# cardV3.net
KiCad netlist of a schematic drawn in EAGLE
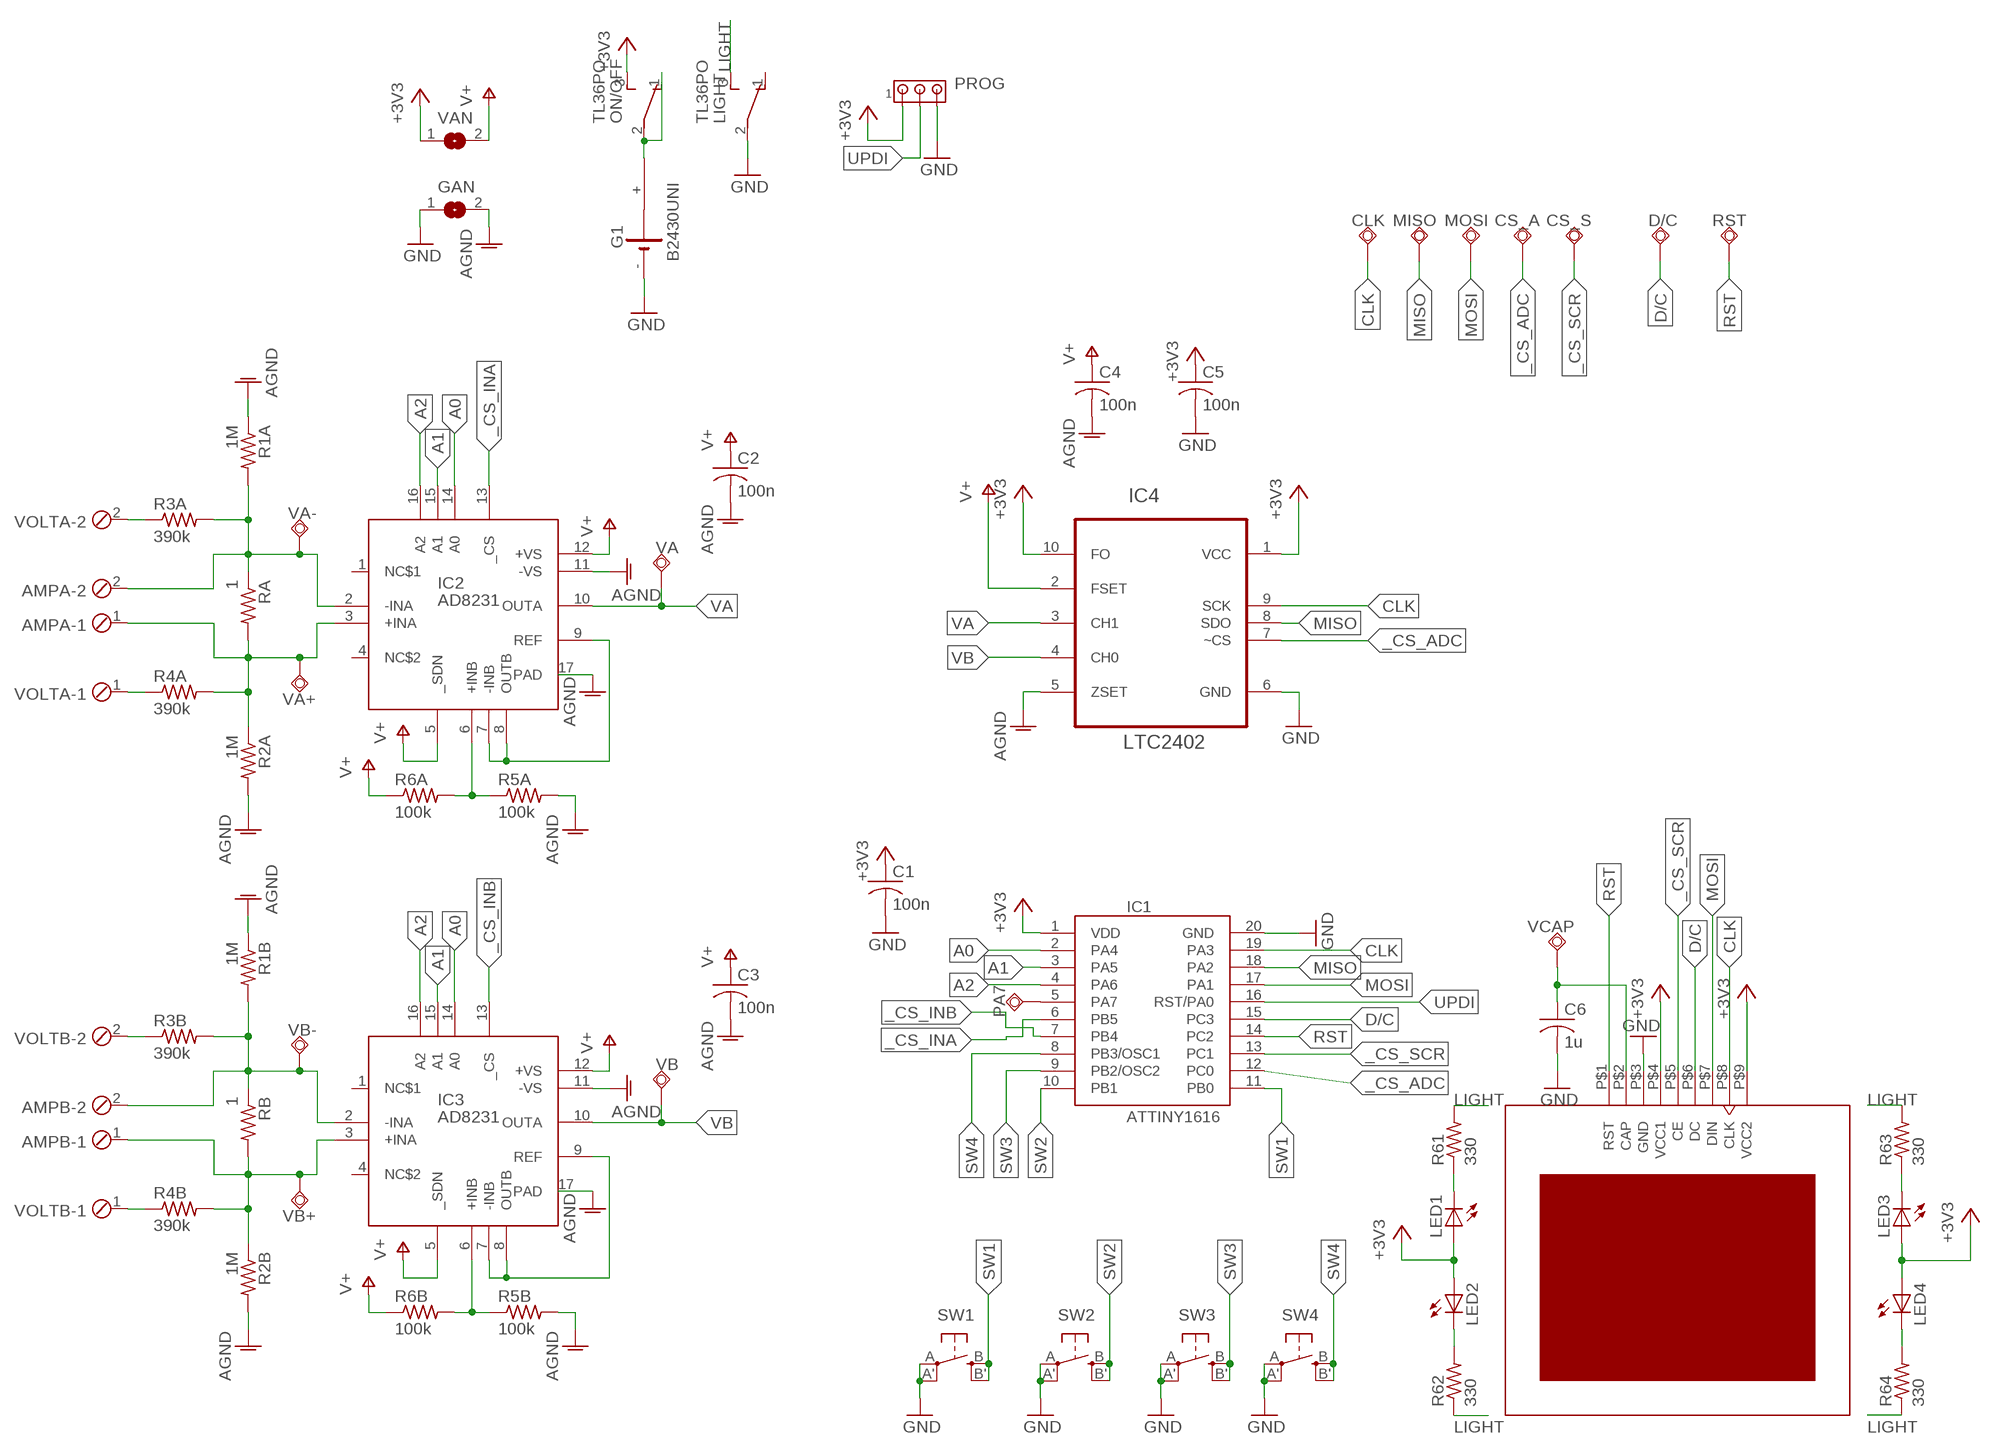
[diagram p0: schematic, sheet 1]

(export (version "E")
  (design (tool "Eeschema 10.0.6"))
  (components
    (comp (ref "AMPA")
      (value "MPT2")
      (footprint "eagle-import:2POL254")
      (libsource (lib "eagle-import") (part "MPT2"))
    )
    (comp (ref "AMPB")
      (value "MPT2")
      (footprint "eagle-import:2POL254")
      (libsource (lib "eagle-import") (part "MPT2"))
    )
    (comp (ref "C1")
      (value "100n")
      (footprint "eagle-import:C0805K")
      (libsource (lib "eagle-import") (part "C-USC0805K"))
    )
    (comp (ref "C2")
      (value "100n")
      (footprint "eagle-import:C0805K")
      (libsource (lib "eagle-import") (part "C-USC0805K"))
    )
    (comp (ref "C3")
      (value "100n")
      (footprint "eagle-import:C0805K")
      (libsource (lib "eagle-import") (part "C-USC0805K"))
    )
    (comp (ref "C4")
      (value "100n")
      (footprint "eagle-import:C0805K")
      (libsource (lib "eagle-import") (part "C-USC0805K"))
    )
    (comp (ref "C5")
      (value "100n")
      (footprint "eagle-import:C0805K")
      (libsource (lib "eagle-import") (part "C-USC0805K"))
    )
    (comp (ref "C6")
      (value "1u")
      (footprint "eagle-import:C0805")
      (libsource (lib "eagle-import") (part "resistor_C-USC0805"))
    )
    (comp (ref "CLK")
      (value "TPSQB1,27")
      (footprint "eagle-import:B1,27")
      (libsource (lib "eagle-import") (part "TPSQB1,27"))
    )
    (comp (ref "CS_A")
      (value "TPSQB1,27")
      (footprint "eagle-import:B1,27")
      (libsource (lib "eagle-import") (part "TPSQB1,27"))
    )
    (comp (ref "CS_S")
      (value "TPSQB1,27")
      (footprint "eagle-import:B1,27")
      (libsource (lib "eagle-import") (part "TPSQB1,27"))
    )
    (comp (ref "D/C")
      (value "TPSQB1,27")
      (footprint "eagle-import:B1,27")
      (libsource (lib "eagle-import") (part "TPSQB1,27"))
    )
    (comp (ref "G1")
      (value "B2430UNI")
      (footprint "eagle-import:B2430UNI")
      (libsource (lib "eagle-import") (part "B2430UNI"))
    )
    (comp (ref "GAN") (value "SJ") (footprint "eagle-import:SJ") (libsource (lib "eagle-import") (part "SJ")))
    (comp (ref "IC1")
      (value "ATTINY1616")
      (footprint "eagle-import:SO20W")
      (libsource (lib "eagle-import") (part "ATTINY1616"))
    )
    (comp (ref "IC2")
      (value "AD8231")
      (footprint "eagle-import:LFCSP16")
      (libsource (lib "eagle-import") (part "AD8231"))
    )
    (comp (ref "IC3")
      (value "AD8231")
      (footprint "eagle-import:LFCSP16")
      (libsource (lib "eagle-import") (part "AD8231"))
    )
    (comp (ref "IC4")
      (value "LTC2402")
      (footprint "eagle-import:MSOP10")
      (libsource (lib "eagle-import") (part "LTC2402CMS"))
    )
    (comp (ref "LED1")
      (value "LEDCHIP-LED0805")
      (footprint "eagle-import:CHIP-LED0805")
      (libsource (lib "eagle-import") (part "LEDCHIP-LED0805"))
    )
    (comp (ref "LED2")
      (value "LEDCHIP-LED0805")
      (footprint "eagle-import:CHIP-LED0805")
      (libsource (lib "eagle-import") (part "LEDCHIP-LED0805"))
    )
    (comp (ref "LED3")
      (value "LEDCHIP-LED0805")
      (footprint "eagle-import:CHIP-LED0805")
      (libsource (lib "eagle-import") (part "LEDCHIP-LED0805"))
    )
    (comp (ref "LED4")
      (value "LEDCHIP-LED0805")
      (footprint "eagle-import:CHIP-LED0805")
      (libsource (lib "eagle-import") (part "LEDCHIP-LED0805"))
    )
    (comp (ref "LIGHT")
      (value "TL36PO")
      (footprint "eagle-import:TL3XPO")
      (libsource (lib "eagle-import") (part "TL36PO"))
    )
    (comp (ref "MISO")
      (value "TPSQB1,27")
      (footprint "eagle-import:B1,27")
      (libsource (lib "eagle-import") (part "TPSQB1,27"))
    )
    (comp (ref "MOSI")
      (value "TPSQB1,27")
      (footprint "eagle-import:B1,27")
      (libsource (lib "eagle-import") (part "TPSQB1,27"))
    )
    (comp (ref "ON/OFF")
      (value "TL36PO")
      (footprint "eagle-import:TL3XPO")
      (libsource (lib "eagle-import") (part "TL36PO"))
    )
    (comp (ref "PA7")
      (value "TPSQB1,27")
      (footprint "eagle-import:B1,27")
      (libsource (lib "eagle-import") (part "TPSQB1,27"))
    )
    (comp (ref "PROG")
      (value "MTA03-100")
      (footprint "eagle-import:10X03MTA")
      (libsource (lib "eagle-import") (part "MTA03-100"))
    )
    (comp (ref "R1A")
      (value "1M")
      (footprint "eagle-import:M0805")
      (libsource (lib "eagle-import") (part "R-US_M0805"))
    )
    (comp (ref "R1B")
      (value "1M")
      (footprint "eagle-import:M0805")
      (libsource (lib "eagle-import") (part "R-US_M0805"))
    )
    (comp (ref "R2A")
      (value "1M")
      (footprint "eagle-import:M0805")
      (libsource (lib "eagle-import") (part "R-US_M0805"))
    )
    (comp (ref "R2B")
      (value "1M")
      (footprint "eagle-import:M0805")
      (libsource (lib "eagle-import") (part "R-US_M0805"))
    )
    (comp (ref "R3A")
      (value "390k")
      (footprint "eagle-import:M0805")
      (libsource (lib "eagle-import") (part "R-US_M0805"))
    )
    (comp (ref "R3B")
      (value "390k")
      (footprint "eagle-import:M0805")
      (libsource (lib "eagle-import") (part "R-US_M0805"))
    )
    (comp (ref "R4A")
      (value "390k")
      (footprint "eagle-import:M0805")
      (libsource (lib "eagle-import") (part "R-US_M0805"))
    )
    (comp (ref "R4B")
      (value "390k")
      (footprint "eagle-import:M0805")
      (libsource (lib "eagle-import") (part "R-US_M0805"))
    )
    (comp (ref "R5A")
      (value "100k")
      (footprint "eagle-import:M0805")
      (libsource (lib "eagle-import") (part "R-US_M0805"))
    )
    (comp (ref "R5B")
      (value "100k")
      (footprint "eagle-import:M0805")
      (libsource (lib "eagle-import") (part "R-US_M0805"))
    )
    (comp (ref "R6A")
      (value "100k")
      (footprint "eagle-import:M0805")
      (libsource (lib "eagle-import") (part "R-US_M0805"))
    )
    (comp (ref "R6B")
      (value "100k")
      (footprint "eagle-import:M0805")
      (libsource (lib "eagle-import") (part "R-US_M0805"))
    )
    (comp (ref "R61")
      (value "330")
      (footprint "eagle-import:M0805")
      (libsource (lib "eagle-import") (part "R-US_M0805"))
    )
    (comp (ref "R62")
      (value "330")
      (footprint "eagle-import:M0805")
      (libsource (lib "eagle-import") (part "R-US_M0805"))
    )
    (comp (ref "R63")
      (value "330")
      (footprint "eagle-import:M0805")
      (libsource (lib "eagle-import") (part "R-US_M0805"))
    )
    (comp (ref "R64")
      (value "330")
      (footprint "eagle-import:M0805")
      (libsource (lib "eagle-import") (part "R-US_M0805"))
    )
    (comp (ref "RA")
      (value "1")
      (footprint "eagle-import:M0805")
      (libsource (lib "eagle-import") (part "R-US_M0805"))
    )
    (comp (ref "RB")
      (value "1")
      (footprint "eagle-import:M0805")
      (libsource (lib "eagle-import") (part "R-US_M0805"))
    )
    (comp (ref "RST")
      (value "TPSQB1,27")
      (footprint "eagle-import:B1,27")
      (libsource (lib "eagle-import") (part "TPSQB1,27"))
    )
    (comp (ref "SCR")
      (value "NOKIA_SCREEN")
      (footprint "eagle-import:NOKIA_SCREEN")
      (libsource (lib "eagle-import") (part "NOKIA_SCREEN"))
    )
    (comp (ref "SW1")
      (value "SPST_TACT-EVQQ2")
      (footprint "eagle-import:EVQ-Q2")
      (libsource (lib "eagle-import") (part "SPST_TACT-EVQQ2"))
    )
    (comp (ref "SW2")
      (value "SPST_TACT-EVQQ2")
      (footprint "eagle-import:EVQ-Q2")
      (libsource (lib "eagle-import") (part "SPST_TACT-EVQQ2"))
    )
    (comp (ref "SW3")
      (value "SPST_TACT-EVQQ2")
      (footprint "eagle-import:EVQ-Q2")
      (libsource (lib "eagle-import") (part "SPST_TACT-EVQQ2"))
    )
    (comp (ref "SW4")
      (value "SPST_TACT-EVQQ2")
      (footprint "eagle-import:EVQ-Q2")
      (libsource (lib "eagle-import") (part "SPST_TACT-EVQQ2"))
    )
    (comp (ref "VA")
      (value "TPSQB1,27")
      (footprint "eagle-import:B1,27")
      (libsource (lib "eagle-import") (part "TPSQB1,27"))
    )
    (comp (ref "VA+")
      (value "TPSQB1,27")
      (footprint "eagle-import:B1,27")
      (libsource (lib "eagle-import") (part "TPSQB1,27"))
    )
    (comp (ref "VA-")
      (value "TPSQB1,27")
      (footprint "eagle-import:B1,27")
      (libsource (lib "eagle-import") (part "TPSQB1,27"))
    )
    (comp (ref "VAN") (value "SJ") (footprint "eagle-import:SJ") (libsource (lib "eagle-import") (part "SJ")))
    (comp (ref "VB")
      (value "TPSQB1,27")
      (footprint "eagle-import:B1,27")
      (libsource (lib "eagle-import") (part "TPSQB1,27"))
    )
    (comp (ref "VB+")
      (value "TPSQB1,27")
      (footprint "eagle-import:B1,27")
      (libsource (lib "eagle-import") (part "TPSQB1,27"))
    )
    (comp (ref "VB-")
      (value "TPSQB1,27")
      (footprint "eagle-import:B1,27")
      (libsource (lib "eagle-import") (part "TPSQB1,27"))
    )
    (comp (ref "VCAP")
      (value "TPSQB1,27")
      (footprint "eagle-import:B1,27")
      (libsource (lib "eagle-import") (part "TPSQB1,27"))
    )
    (comp (ref "VOLTA")
      (value "MPT2")
      (footprint "eagle-import:2POL254")
      (libsource (lib "eagle-import") (part "MPT2"))
    )
    (comp (ref "VOLTB")
      (value "MPT2")
      (footprint "eagle-import:2POL254")
      (libsource (lib "eagle-import") (part "MPT2"))
    )
  )
  (nets
    (net (code "1") (name "+3V3") (class "Default")
      (node (ref "C1") (pin "1") (pinfunction "1_1") (pintype "passive"))
      (node (ref "C5") (pin "1") (pinfunction "1_1") (pintype "passive"))
      (node (ref "IC1") (pin "1") (pinfunction "VDD_1") (pintype "power_in"))
      (node (ref "IC4") (pin "1") (pinfunction "VCC_1") (pintype "power_in"))
      (node (ref "IC4") (pin "10") (pinfunction "FO_10") (pintype "input"))
      (node (ref "LED1") (pin "A") (pinfunction "A_A") (pintype "passive"))
      (node (ref "LED2") (pin "A") (pinfunction "A_A") (pintype "passive"))
      (node (ref "LED3") (pin "A") (pinfunction "A_A") (pintype "passive"))
      (node (ref "LED4") (pin "A") (pinfunction "A_A") (pintype "passive"))
      (node (ref "ON/OFF") (pin "3") (pinfunction "S_3") (pintype "passive"))
      (node (ref "PROG") (pin "1") (pinfunction "1_1") (pintype "passive"))
      (node (ref "SCR") (pin "P$4") (pinfunction "VCC1_P$4") (pintype "power_in"))
      (node (ref "SCR") (pin "P$9") (pinfunction "VCC2_P$9") (pintype "power_in"))
      (node (ref "VAN") (pin "1") (pinfunction "1_1") (pintype "passive"))
    )
    (net (code "2") (name "/LIGHT") (class "Default")
      (node (ref "LIGHT") (pin "3") (pinfunction "S_3") (pintype "passive"))
      (node (ref "R61") (pin "2") (pinfunction "2_2") (pintype "passive"))
      (node (ref "R62") (pin "1") (pinfunction "1_1") (pintype "passive"))
      (node (ref "R63") (pin "2") (pinfunction "2_2") (pintype "passive"))
      (node (ref "R64") (pin "1") (pinfunction "1_1") (pintype "passive"))
    )
    (net (code "3") (name "A0") (class "Default")
      (node (ref "IC1") (pin "2") (pinfunction "PA4_2") (pintype "bidirectional"))
      (node (ref "IC2") (pin "14") (pinfunction "A0_14") (pintype "input"))
      (node (ref "IC3") (pin "14") (pinfunction "A0_14") (pintype "input"))
    )
    (net (code "4") (name "A1") (class "Default")
      (node (ref "IC1") (pin "3") (pinfunction "PA5_3") (pintype "bidirectional"))
      (node (ref "IC2") (pin "15") (pinfunction "A1_15") (pintype "input"))
      (node (ref "IC3") (pin "15") (pinfunction "A1_15") (pintype "input"))
    )
    (net (code "5") (name "A2") (class "Default")
      (node (ref "IC1") (pin "4") (pinfunction "PA6_4") (pintype "bidirectional"))
      (node (ref "IC2") (pin "16") (pinfunction "A2_16") (pintype "input"))
      (node (ref "IC3") (pin "16") (pinfunction "A2_16") (pintype "input"))
    )
    (net (code "6") (name "AGND") (class "Default")
      (node (ref "C2") (pin "2") (pinfunction "2_2") (pintype "passive"))
      (node (ref "C3") (pin "2") (pinfunction "2_2") (pintype "passive"))
      (node (ref "C4") (pin "2") (pinfunction "2_2") (pintype "passive"))
      (node (ref "GAN") (pin "2") (pinfunction "2_2") (pintype "passive"))
      (node (ref "IC2") (pin "11") (pinfunction "-VS_11") (pintype "power_in"))
      (node (ref "IC2") (pin "17") (pinfunction "PAD_17") (pintype "power_in"))
      (node (ref "IC3") (pin "11") (pinfunction "-VS_11") (pintype "power_in"))
      (node (ref "IC3") (pin "17") (pinfunction "PAD_17") (pintype "power_in"))
      (node (ref "IC4") (pin "5") (pinfunction "ZSET_5") (pintype "input"))
      (node (ref "R1A") (pin "1") (pinfunction "1_1") (pintype "passive"))
      (node (ref "R1B") (pin "1") (pinfunction "1_1") (pintype "passive"))
      (node (ref "R2A") (pin "2") (pinfunction "2_2") (pintype "passive"))
      (node (ref "R2B") (pin "2") (pinfunction "2_2") (pintype "passive"))
      (node (ref "R5A") (pin "2") (pinfunction "2_2") (pintype "passive"))
      (node (ref "R5B") (pin "2") (pinfunction "2_2") (pintype "passive"))
    )
    (net (code "7") (name "CLK") (class "Default")
      (node (ref "CLK") (pin "TP") (pinfunction "TP_TP") (pintype "input"))
      (node (ref "IC1") (pin "19") (pinfunction "PA3_19") (pintype "bidirectional"))
      (node (ref "IC4") (pin "9") (pinfunction "SCK_9") (pintype "input"))
      (node (ref "SCR") (pin "P$8") (pinfunction "CLK_P$8") (pintype "input"))
    )
    (net (code "8") (name "D{slash}C") (class "Default")
      (node (ref "D/C") (pin "TP") (pinfunction "TP_TP") (pintype "input"))
      (node (ref "IC1") (pin "15") (pinfunction "PC3_15") (pintype "bidirectional"))
      (node (ref "SCR") (pin "P$6") (pinfunction "DC_P$6") (pintype "input"))
    )
    (net (code "9") (name "GND") (class "Default")
      (node (ref "C1") (pin "2") (pinfunction "2_2") (pintype "passive"))
      (node (ref "C5") (pin "2") (pinfunction "2_2") (pintype "passive"))
      (node (ref "C6") (pin "2") (pinfunction "2_2") (pintype "passive"))
      (node (ref "G1") (pin "-") (pinfunction "-_-") (pintype "passive"))
      (node (ref "GAN") (pin "1") (pinfunction "1_1") (pintype "passive"))
      (node (ref "IC1") (pin "20") (pinfunction "GND_20") (pintype "power_in"))
      (node (ref "IC4") (pin "6") (pinfunction "GND_6") (pintype "passive"))
      (node (ref "LIGHT") (pin "2") (pinfunction "P_2") (pintype "passive"))
      (node (ref "PROG") (pin "3") (pinfunction "3_3") (pintype "passive"))
      (node (ref "SCR") (pin "P$3") (pinfunction "GND_P$3") (pintype "power_in"))
      (node (ref "SW1") (pin "A") (pinfunction "P_A") (pintype "passive"))
      (node (ref "SW1") (pin "A'") (pinfunction "P1_A'") (pintype "passive"))
      (node (ref "SW2") (pin "A") (pinfunction "P_A") (pintype "passive"))
      (node (ref "SW2") (pin "A'") (pinfunction "P1_A'") (pintype "passive"))
      (node (ref "SW3") (pin "A") (pinfunction "P_A") (pintype "passive"))
      (node (ref "SW3") (pin "A'") (pinfunction "P1_A'") (pintype "passive"))
      (node (ref "SW4") (pin "A") (pinfunction "P_A") (pintype "passive"))
      (node (ref "SW4") (pin "A'") (pinfunction "P1_A'") (pintype "passive"))
    )
    (net (code "10") (name "MISO") (class "Default")
      (node (ref "IC1") (pin "18") (pinfunction "PA2_18") (pintype "bidirectional"))
      (node (ref "IC4") (pin "8") (pinfunction "SDO_8") (pintype "output"))
      (node (ref "MISO") (pin "TP") (pinfunction "TP_TP") (pintype "input"))
    )
    (net (code "11") (name "MOSI") (class "Default")
      (node (ref "IC1") (pin "17") (pinfunction "PA1_17") (pintype "bidirectional"))
      (node (ref "MOSI") (pin "TP") (pinfunction "TP_TP") (pintype "input"))
      (node (ref "SCR") (pin "P$7") (pinfunction "DIN_P$7") (pintype "input"))
    )
    (net (code "12") (name "Net-(AMPAB-1)") (class "Default")
      (node (ref "AMPA") (pin "2") (pinfunction "1_2") (pintype "passive"))
      (node (ref "IC2") (pin "2") (pinfunction "-INA_2") (pintype "input"))
      (node (ref "R1A") (pin "2") (pinfunction "2_2") (pintype "passive"))
      (node (ref "R3A") (pin "2") (pinfunction "2_2") (pintype "passive"))
      (node (ref "RA") (pin "1") (pinfunction "1_1") (pintype "passive"))
      (node (ref "VA-") (pin "TP") (pinfunction "TP_TP") (pintype "input"))
    )
    (net (code "13") (name "Net-(AMPBB-1)") (class "Default")
      (node (ref "AMPB") (pin "2") (pinfunction "1_2") (pintype "passive"))
      (node (ref "IC3") (pin "2") (pinfunction "-INA_2") (pintype "input"))
      (node (ref "R1B") (pin "2") (pinfunction "2_2") (pintype "passive"))
      (node (ref "R3B") (pin "2") (pinfunction "2_2") (pintype "passive"))
      (node (ref "RB") (pin "1") (pinfunction "1_1") (pintype "passive"))
      (node (ref "VB-") (pin "TP") (pinfunction "TP_TP") (pintype "input"))
    )
    (net (code "14") (name "Net-(IC1-PA7)") (class "Default")
      (node (ref "IC1") (pin "5") (pinfunction "PA7_5") (pintype "bidirectional"))
      (node (ref "PA7") (pin "TP") (pinfunction "TP_TP") (pintype "input"))
    )
    (net (code "15") (name "Net-(IC2-+INA)") (class "Default")
      (node (ref "AMPA") (pin "1") (pinfunction "1_1") (pintype "passive"))
      (node (ref "IC2") (pin "3") (pinfunction "+INA_3") (pintype "input"))
      (node (ref "R2A") (pin "1") (pinfunction "1_1") (pintype "passive"))
      (node (ref "R4A") (pin "2") (pinfunction "2_2") (pintype "passive"))
      (node (ref "RA") (pin "2") (pinfunction "2_2") (pintype "passive"))
      (node (ref "VA+") (pin "TP") (pinfunction "TP_TP") (pintype "input"))
    )
    (net (code "16") (name "Net-(IC2-+INB)") (class "Default")
      (node (ref "IC2") (pin "6") (pinfunction "+INB_6") (pintype "input"))
      (node (ref "R5A") (pin "1") (pinfunction "1_1") (pintype "passive"))
      (node (ref "R6A") (pin "2") (pinfunction "2_2") (pintype "passive"))
    )
    (net (code "17") (name "Net-(IC2--INB)") (class "Default")
      (node (ref "IC2") (pin "7") (pinfunction "-INB_7") (pintype "input"))
      (node (ref "IC2") (pin "8") (pinfunction "OUTB_8") (pintype "output"))
      (node (ref "IC2") (pin "9") (pinfunction "REF_9") (pintype "input"))
    )
    (net (code "18") (name "Net-(IC3-+INA)") (class "Default")
      (node (ref "AMPB") (pin "1") (pinfunction "1_1") (pintype "passive"))
      (node (ref "IC3") (pin "3") (pinfunction "+INA_3") (pintype "input"))
      (node (ref "R2B") (pin "1") (pinfunction "1_1") (pintype "passive"))
      (node (ref "R4B") (pin "2") (pinfunction "2_2") (pintype "passive"))
      (node (ref "RB") (pin "2") (pinfunction "2_2") (pintype "passive"))
      (node (ref "VB+") (pin "TP") (pinfunction "TP_TP") (pintype "input"))
    )
    (net (code "19") (name "Net-(IC3-+INB)") (class "Default")
      (node (ref "IC3") (pin "6") (pinfunction "+INB_6") (pintype "input"))
      (node (ref "R5B") (pin "1") (pinfunction "1_1") (pintype "passive"))
      (node (ref "R6B") (pin "2") (pinfunction "2_2") (pintype "passive"))
    )
    (net (code "20") (name "Net-(IC3--INB)") (class "Default")
      (node (ref "IC3") (pin "7") (pinfunction "-INB_7") (pintype "input"))
      (node (ref "IC3") (pin "8") (pinfunction "OUTB_8") (pintype "output"))
      (node (ref "IC3") (pin "9") (pinfunction "REF_9") (pintype "input"))
    )
    (net (code "21") (name "Net-(LED1-PadC)") (class "Default")
      (node (ref "LED1") (pin "C") (pinfunction "C_C") (pintype "passive"))
      (node (ref "R61") (pin "1") (pinfunction "1_1") (pintype "passive"))
    )
    (net (code "22") (name "Net-(LED2-PadC)") (class "Default")
      (node (ref "LED2") (pin "C") (pinfunction "C_C") (pintype "passive"))
      (node (ref "R62") (pin "2") (pinfunction "2_2") (pintype "passive"))
    )
    (net (code "23") (name "Net-(LED3-PadC)") (class "Default")
      (node (ref "LED3") (pin "C") (pinfunction "C_C") (pintype "passive"))
      (node (ref "R63") (pin "1") (pinfunction "1_1") (pintype "passive"))
    )
    (net (code "24") (name "Net-(LED4-PadC)") (class "Default")
      (node (ref "LED4") (pin "C") (pinfunction "C_C") (pintype "passive"))
      (node (ref "R64") (pin "2") (pinfunction "2_2") (pintype "passive"))
    )
    (net (code "25") (name "Net-(ON/OFF-O)") (class "Default")
      (node (ref "G1") (pin "+") (pinfunction "+_+") (pintype "passive"))
      (node (ref "ON/OFF") (pin "1") (pinfunction "O_1") (pintype "passive"))
      (node (ref "ON/OFF") (pin "2") (pinfunction "P_2") (pintype "passive"))
    )
    (net (code "26") (name "Net-(R4A-Pad1)") (class "Default")
      (node (ref "R4A") (pin "1") (pinfunction "1_1") (pintype "passive"))
      (node (ref "VOLTA") (pin "1") (pinfunction "1_1") (pintype "passive"))
    )
    (net (code "27") (name "Net-(R4B-Pad1)") (class "Default")
      (node (ref "R4B") (pin "1") (pinfunction "1_1") (pintype "passive"))
      (node (ref "VOLTB") (pin "1") (pinfunction "1_1") (pintype "passive"))
    )
    (net (code "28") (name "Net-(SCR-CAP)") (class "Default")
      (node (ref "C6") (pin "1") (pinfunction "1_1") (pintype "passive"))
      (node (ref "SCR") (pin "P$2") (pinfunction "CAP_P$2") (pintype "passive"))
      (node (ref "VCAP") (pin "TP") (pinfunction "TP_TP") (pintype "input"))
    )
    (net (code "29") (name "Net-(VOLTAB-1)") (class "Default")
      (node (ref "R3A") (pin "1") (pinfunction "1_1") (pintype "passive"))
      (node (ref "VOLTA") (pin "2") (pinfunction "1_2") (pintype "passive"))
    )
    (net (code "30") (name "Net-(VOLTBB-1)") (class "Default")
      (node (ref "R3B") (pin "1") (pinfunction "1_1") (pintype "passive"))
      (node (ref "VOLTB") (pin "2") (pinfunction "1_2") (pintype "passive"))
    )
    (net (code "31") (name "RST") (class "Default")
      (node (ref "IC1") (pin "14") (pinfunction "PC2_14") (pintype "bidirectional"))
      (node (ref "RST") (pin "TP") (pinfunction "TP_TP") (pintype "input"))
      (node (ref "SCR") (pin "P$1") (pinfunction "RST_P$1") (pintype "input"))
    )
    (net (code "32") (name "SW1") (class "Default")
      (node (ref "IC1") (pin "11") (pinfunction "PB0_11") (pintype "bidirectional"))
      (node (ref "SW1") (pin "B") (pinfunction "S_B") (pintype "passive"))
      (node (ref "SW1") (pin "B'") (pinfunction "S1_B'") (pintype "passive"))
    )
    (net (code "33") (name "SW2") (class "Default")
      (node (ref "IC1") (pin "10") (pinfunction "PB1_10") (pintype "bidirectional"))
      (node (ref "SW2") (pin "B") (pinfunction "S_B") (pintype "passive"))
      (node (ref "SW2") (pin "B'") (pinfunction "S1_B'") (pintype "passive"))
    )
    (net (code "34") (name "SW3") (class "Default")
      (node (ref "IC1") (pin "9") (pinfunction "PB2/OSC2_9") (pintype "bidirectional"))
      (node (ref "SW3") (pin "B") (pinfunction "S_B") (pintype "passive"))
      (node (ref "SW3") (pin "B'") (pinfunction "S1_B'") (pintype "passive"))
    )
    (net (code "35") (name "SW4") (class "Default")
      (node (ref "IC1") (pin "8") (pinfunction "PB3/OSC1_8") (pintype "bidirectional"))
      (node (ref "SW4") (pin "B") (pinfunction "S_B") (pintype "passive"))
      (node (ref "SW4") (pin "B'") (pinfunction "S1_B'") (pintype "passive"))
    )
    (net (code "36") (name "UPDI") (class "Default")
      (node (ref "IC1") (pin "16") (pinfunction "RST/PA0_16") (pintype "bidirectional"))
      (node (ref "PROG") (pin "2") (pinfunction "2_2") (pintype "passive"))
    )
    (net (code "37") (name "V+") (class "Default")
      (node (ref "C2") (pin "1") (pinfunction "1_1") (pintype "passive"))
      (node (ref "C3") (pin "1") (pinfunction "1_1") (pintype "passive"))
      (node (ref "C4") (pin "1") (pinfunction "1_1") (pintype "passive"))
      (node (ref "IC2") (pin "12") (pinfunction "+VS_12") (pintype "power_in"))
      (node (ref "IC2") (pin "5") (pinfunction "_SDN_5") (pintype "input"))
      (node (ref "IC3") (pin "12") (pinfunction "+VS_12") (pintype "power_in"))
      (node (ref "IC3") (pin "5") (pinfunction "_SDN_5") (pintype "input"))
      (node (ref "IC4") (pin "2") (pinfunction "FSET_2") (pintype "input"))
      (node (ref "R6A") (pin "1") (pinfunction "1_1") (pintype "passive"))
      (node (ref "R6B") (pin "1") (pinfunction "1_1") (pintype "passive"))
      (node (ref "VAN") (pin "2") (pinfunction "2_2") (pintype "passive"))
    )
    (net (code "38") (name "VA") (class "Default")
      (node (ref "IC2") (pin "10") (pinfunction "OUTA_10") (pintype "output"))
      (node (ref "IC4") (pin "3") (pinfunction "CH1_3") (pintype "input"))
      (node (ref "VA") (pin "TP") (pinfunction "TP_TP") (pintype "input"))
    )
    (net (code "39") (name "VB") (class "Default")
      (node (ref "IC3") (pin "10") (pinfunction "OUTA_10") (pintype "output"))
      (node (ref "IC4") (pin "4") (pinfunction "CH0_4") (pintype "input"))
      (node (ref "VB") (pin "TP") (pinfunction "TP_TP") (pintype "input"))
    )
    (net (code "40") (name "_CS_ADC") (class "Default")
      (node (ref "CS_A") (pin "TP") (pinfunction "TP_TP") (pintype "input"))
      (node (ref "IC1") (pin "12") (pinfunction "PC0_12") (pintype "bidirectional"))
      (node (ref "IC4") (pin "7") (pinfunction "~{CS}_7") (pintype "input"))
    )
    (net (code "41") (name "_CS_INA") (class "Default")
      (node (ref "IC1") (pin "6") (pinfunction "PB5_6") (pintype "bidirectional"))
      (node (ref "IC2") (pin "13") (pinfunction "_CS_13") (pintype "input"))
    )
    (net (code "42") (name "_CS_INB") (class "Default")
      (node (ref "IC1") (pin "7") (pinfunction "PB4_7") (pintype "bidirectional"))
      (node (ref "IC3") (pin "13") (pinfunction "_CS_13") (pintype "input"))
    )
    (net (code "43") (name "_CS_SCR") (class "Default")
      (node (ref "CS_S") (pin "TP") (pinfunction "TP_TP") (pintype "input"))
      (node (ref "IC1") (pin "13") (pinfunction "PC1_13") (pintype "bidirectional"))
      (node (ref "SCR") (pin "P$5") (pinfunction "CE_P$5") (pintype "input"))
    )
    (net (code "44") (name "unconnected-(G1-+-Pad+@1)") (class "Default")
      (node (ref "G1") (pin "+@1") (pinfunction "+_+@1") (pintype "passive"))
    )
    (net (code "45") (name "unconnected-(G1-+-Pad+@2)") (class "Default")
      (node (ref "G1") (pin "+@2") (pinfunction "+_+@2") (pintype "passive"))
    )
    (net (code "46") (name "unconnected-(G1-+-Pad+@3)") (class "Default")
      (node (ref "G1") (pin "+@3") (pinfunction "+_+@3") (pintype "passive"))
    )
    (net (code "47") (name "unconnected-(G1-+-Pad+@4)") (class "Default")
      (node (ref "G1") (pin "+@4") (pinfunction "+_+@4") (pintype "passive"))
    )
    (net (code "48") (name "unconnected-(G1---Pad-@1)") (class "Default")
      (node (ref "G1") (pin "-@1") (pinfunction "-_-@1") (pintype "passive"))
    )
    (net (code "49") (name "unconnected-(IC2-NC$1-Pad1)") (class "Default")
      (node (ref "IC2") (pin "1") (pinfunction "NC$1_1") (pintype "no_connect"))
    )
    (net (code "50") (name "unconnected-(IC2-NC$2-Pad4)") (class "Default")
      (node (ref "IC2") (pin "4") (pinfunction "NC$2_4") (pintype "no_connect"))
    )
    (net (code "51") (name "unconnected-(IC3-NC$1-Pad1)") (class "Default")
      (node (ref "IC3") (pin "1") (pinfunction "NC$1_1") (pintype "no_connect"))
    )
    (net (code "52") (name "unconnected-(IC3-NC$2-Pad4)") (class "Default")
      (node (ref "IC3") (pin "4") (pinfunction "NC$2_4") (pintype "no_connect"))
    )
    (net (code "53") (name "unconnected-(LIGHT-O-Pad1)") (class "Default")
      (node (ref "LIGHT") (pin "1") (pinfunction "O_1") (pintype "passive"))
    )
  )
)
